# STM32H7-Board.net
KiCad netlist of a schematic drawn in Altium Designer
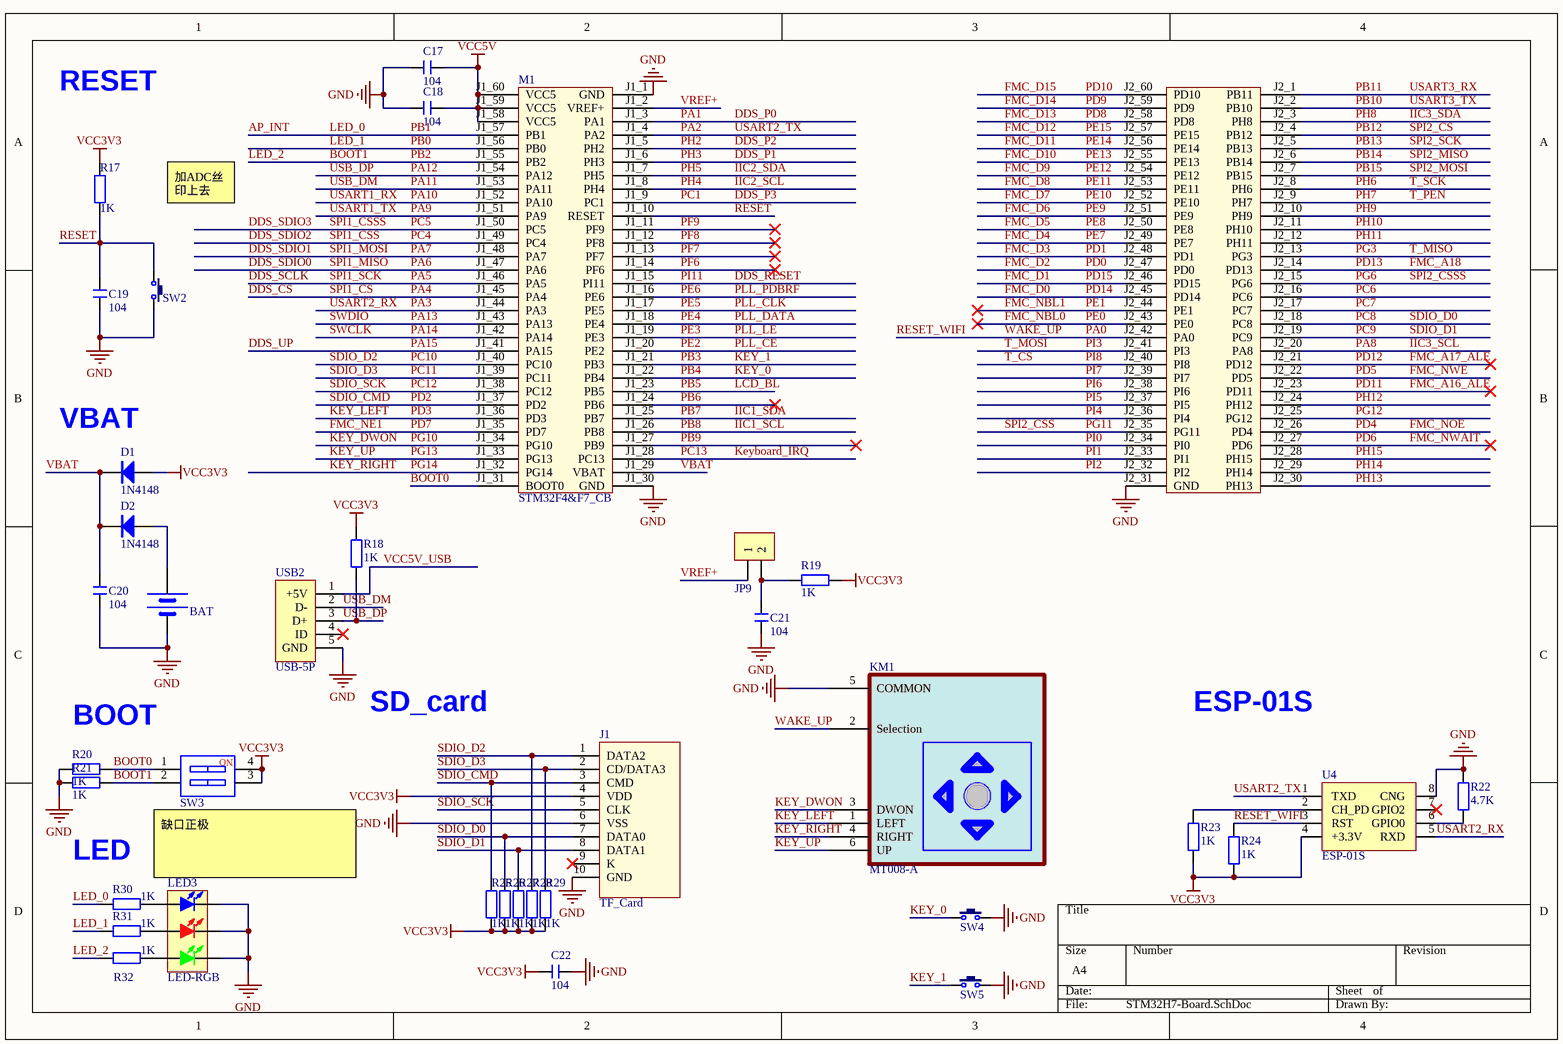
[diagram p0: STM32H7-Board.SchDoc]

(export (version "E")
  (design (tool "Eeschema 10.0.6"))
  (components
    (comp (ref "BAT") (value "BATT") (footprint "BATM") (libsource (lib "MERCURY") (part "BAT")))
    (comp (ref "C17")
      (value "104")
      (footprint "C 0603_L")
      (description "无极性贴片电容")
      (fields (field (name "版权归属") "源创客"))
      (libsource (lib "3.1   - 电阻-电容-电感") (part "C"))
    )
    (comp (ref "C18")
      (value "104")
      (footprint "C 0603_L")
      (description "无极性贴片电容")
      (fields (field (name "版权归属") "源创客"))
      (libsource (lib "3.1   - 电阻-电容-电感") (part "C"))
    )
    (comp (ref "C19")
      (value "104")
      (footprint "C 0603_L")
      (description "无极性贴片电容")
      (fields (field (name "版权归属") "源创客"))
      (libsource (lib "3.1   - 电阻-电容-电感") (part "C"))
    )
    (comp (ref "C20")
      (value "104")
      (footprint "C 0603_L")
      (description "无极性贴片电容")
      (fields (field (name "版权归属") "源创客"))
      (libsource (lib "3.1   - 电阻-电容-电感") (part "C"))
    )
    (comp (ref "C21")
      (value "104")
      (footprint "C 0603_L")
      (description "无极性贴片电容")
      (fields (field (name "版权归属") "源创客"))
      (libsource (lib "3.1   - 电阻-电容-电感") (part "C"))
    )
    (comp (ref "C22")
      (value "104")
      (footprint "C 0603_L")
      (description "无极性贴片电容")
      (fields (field (name "版权归属") "源创客"))
      (libsource (lib "电阻-电容-电感") (part "C"))
    )
    (comp (ref "D1")
      (value "1N4148")
      (footprint "SOD-323")
      (description "高速开关二极管")
      (fields (field (name "版权归属") "源创客"))
      (libsource (lib "8.1   - 二极管-整流桥") (part "1N4148"))
    )
    (comp (ref "D2")
      (value "1N4148")
      (footprint "MINI_MELF (LL34)")
      (description "高速开关二极管")
      (fields (field (name "版权归属") "源创客"))
      (libsource (lib "8.1   - 二极管-整流桥") (part "1N4148"))
    )
    (comp (ref "J1")
      (value "TF_Card")
      (footprint "Micro SD")
      (description "TF卡座")
      (fields (field (name "版权归属") "源创客"))
      (libsource (lib "4.1   - 接口类") (part "TF_Card"))
    )
    (comp (ref "JP9")
      (value "HDR-1X2")
      (footprint "HDR2.54-LI-2P")
      (description "2P接插件")
      (fields (field (name "版权归属") "源创客"))
      (libsource (lib "4.5   - 接插件-脚距2.54") (part "Header 2"))
    )
    (comp (ref "KM1")
      (value "MT008-A")
      (footprint "JOY_MT008-A")
      (libsource (lib "13.1 - 模块") (part "MT-008A"))
    )
    (comp (ref "LED3")
      (value "LED-RGB")
      (footprint "LED 5050")
      (description "三基色LED")
      (fields (field (name "版权归属") "源创客"))
      (libsource (lib "LED") (part "LED-RGB"))
    )
    (comp (ref "M1")
      (value "STM32F4&F7_CB")
      (footprint "STM32F4&F7_CB")
      (description "F429/746 Core Board")
      (libsource (lib "MERCURY") (part "STM32F4&F7_CB"))
    )
    (comp (ref "R17")
      (value "1K")
      (footprint "R 0603_L")
      (description "贴片电阻")
      (fields (field (name "版权归属") "源创客"))
      (libsource (lib "电阻-电容-电感") (part "R"))
    )
    (comp (ref "R18")
      (value "1K")
      (footprint "R 0603_L")
      (description "贴片电阻")
      (fields (field (name "版权归属") "源创客"))
      (libsource (lib "3.1   - 电阻-电容-电感") (part "R"))
    )
    (comp (ref "R19")
      (value "1K")
      (footprint "R 0603_L")
      (description "贴片电阻")
      (fields (field (name "版权归属") "源创客"))
      (libsource (lib "3.1   - 电阻-电容-电感") (part "R"))
    )
    (comp (ref "R20")
      (value "1K")
      (footprint "R 0603_L")
      (description "贴片电阻")
      (fields (field (name "版权归属") "源创客"))
      (libsource (lib "3.1   - 电阻-电容-电感") (part "R"))
    )
    (comp (ref "R21")
      (value "1K")
      (footprint "R 0603_L")
      (description "贴片电阻")
      (fields (field (name "版权归属") "源创客"))
      (libsource (lib "3.1   - 电阻-电容-电感") (part "R"))
    )
    (comp (ref "R22")
      (value "4.7K")
      (footprint "R 0603_L")
      (description "贴片电阻")
      (fields (field (name "版权归属") "源创客"))
      (libsource (lib "3.1   - 电阻-电容-电感") (part "R"))
    )
    (comp (ref "R23")
      (value "1K")
      (footprint "R 0603_L")
      (description "贴片电阻")
      (fields (field (name "版权归属") "源创客"))
      (libsource (lib "3.1   - 电阻-电容-电感") (part "R"))
    )
    (comp (ref "R24")
      (value "1K")
      (footprint "R 0603_L")
      (description "贴片电阻")
      (fields (field (name "版权归属") "源创客"))
      (libsource (lib "3.1   - 电阻-电容-电感") (part "R"))
    )
    (comp (ref "R25")
      (value "1K")
      (footprint "R 0603_L")
      (description "贴片电阻")
      (fields (field (name "版权归属") "源创客"))
      (libsource (lib "电阻-电容-电感") (part "R"))
    )
    (comp (ref "R26")
      (value "1K")
      (footprint "R 0603_L")
      (description "贴片电阻")
      (fields (field (name "版权归属") "源创客"))
      (libsource (lib "电阻-电容-电感") (part "R"))
    )
    (comp (ref "R27")
      (value "1K")
      (footprint "R 0603_L")
      (description "贴片电阻")
      (fields (field (name "版权归属") "源创客"))
      (libsource (lib "电阻-电容-电感") (part "R"))
    )
    (comp (ref "R28")
      (value "1K")
      (footprint "R 0603_L")
      (description "贴片电阻")
      (fields (field (name "版权归属") "源创客"))
      (libsource (lib "电阻-电容-电感") (part "R"))
    )
    (comp (ref "R29")
      (value "1K")
      (footprint "R 0603_L")
      (description "贴片电阻")
      (fields (field (name "版权归属") "源创客"))
      (libsource (lib "电阻-电容-电感") (part "R"))
    )
    (comp (ref "R30")
      (value "1K")
      (footprint "R 0603_L")
      (description "贴片电阻")
      (fields (field (name "版权归属") "源创客"))
      (libsource (lib "3.1   - 电阻-电容-电感") (part "R"))
    )
    (comp (ref "R31")
      (value "1K")
      (footprint "R 0603_L")
      (description "贴片电阻")
      (fields (field (name "版权归属") "源创客"))
      (libsource (lib "3.1   - 电阻-电容-电感") (part "R"))
    )
    (comp (ref "R32")
      (value "1K")
      (footprint "R 0603_L")
      (description "贴片电阻")
      (fields (field (name "版权归属") "源创客"))
      (libsource (lib "3.1   - 电阻-电容-电感") (part "R"))
    )
    (comp (ref "SW2")
      (value "3x6x5")
      (footprint "TSW SMD-3*6*2.5")
      (description "3x6轻触开关")
      (fields (field (name "版权归属") "源创客"))
      (libsource (lib "") (part "TSW 3x6_1"))
    )
    (comp (ref "SW3")
      (value "CSW-2P")
      (footprint "CSW1.27 SMD-2P")
      (description "2路编码开关")
      (fields (field (name "版权归属") "源创客"))
      (libsource (lib "5.1   - 按键-开关") (part "CSW-2P"))
    )
    (comp (ref "SW4")
      (value "3x6x5")
      (footprint "SODFL700X110-2N")
      (description "3x6轻触开关")
      (fields (field (name "版权归属") "源创客"))
      (libsource (lib "5.1   - 按键-开关") (part "TSW 3x6"))
    )
    (comp (ref "SW5")
      (value "3x6x5")
      (footprint "SODFL700X110-2N")
      (description "3x6轻触开关")
      (fields (field (name "版权归属") "源创客"))
      (libsource (lib "5.1   - 按键-开关") (part "TSW 3x6"))
    )
    (comp (ref "U4") (value "ESP-01S") (footprint "ESP-01S") (libsource (lib "13.1 - 模块") (part "ESP-01S")))
    (comp (ref "USB2")
      (value "USB-5P")
      (footprint "USB-MICRO_B")
      (description "微型USB母座")
      (fields (field (name "版权归属") "源创客"))
      (libsource (lib "4.1   - 接口类") (part "USB-5P"))
    )
  )
  (nets
    (net (code "1") (name "/AP_INT") (class "Default")
      (node (ref "M1") (pin "J1_57") (pinfunction "PB1_J1_57") (pintype "passive"))
      (node (ref "R30") (pin "2") (pinfunction "2_2") (pintype "passive"))
    )
    (net (code "2") (name "/BOOT0") (class "Default")
      (node (ref "M1") (pin "J1_31") (pinfunction "BOOT0_J1_31") (pintype "passive"))
      (node (ref "R20") (pin "2") (pinfunction "2_2") (pintype "passive"))
      (node (ref "SW3") (pin "1") (pinfunction "1_1") (pintype "passive"))
    )
    (net (code "3") (name "/BOOT1") (class "Default")
      (node (ref "M1") (pin "J1_55") (pinfunction "PB2_J1_55") (pintype "passive"))
      (node (ref "R21") (pin "2") (pinfunction "2_2") (pintype "passive"))
      (node (ref "R32") (pin "2") (pinfunction "2_2") (pintype "passive"))
      (node (ref "SW3") (pin "2") (pinfunction "2_2") (pintype "passive"))
    )
    (net (code "4") (name "/DDS_CS") (class "Default")
      (node (ref "M1") (pin "J1_45") (pinfunction "PA4_J1_45") (pintype "passive"))
    )
    (net (code "5") (name "/DDS_P0") (class "Default")
      (node (ref "M1") (pin "J1_3") (pinfunction "PA1_J1_3") (pintype "passive"))
    )
    (net (code "6") (name "/DDS_P1") (class "Default")
      (node (ref "M1") (pin "J1_6") (pinfunction "PH3_J1_6") (pintype "passive"))
    )
    (net (code "7") (name "/DDS_P2") (class "Default")
      (node (ref "M1") (pin "J1_5") (pinfunction "PH2_J1_5") (pintype "passive"))
    )
    (net (code "8") (name "/DDS_P3") (class "Default")
      (node (ref "M1") (pin "J1_9") (pinfunction "PC1_J1_9") (pintype "passive"))
    )
    (net (code "9") (name "/DDS_RESET") (class "Default")
      (node (ref "M1") (pin "J1_15") (pinfunction "PI11_J1_15") (pintype "passive"))
    )
    (net (code "10") (name "/DDS_SCLK") (class "Default")
      (node (ref "M1") (pin "J1_46") (pinfunction "PA5_J1_46") (pintype "passive"))
    )
    (net (code "11") (name "/DDS_SDIO0") (class "Default")
      (node (ref "M1") (pin "J1_47") (pinfunction "PA6_J1_47") (pintype "passive"))
    )
    (net (code "12") (name "/DDS_SDIO1") (class "Default")
      (node (ref "M1") (pin "J1_48") (pinfunction "PA7_J1_48") (pintype "passive"))
    )
    (net (code "13") (name "/DDS_SDIO2") (class "Default")
      (node (ref "M1") (pin "J1_49") (pinfunction "PC4_J1_49") (pintype "passive"))
    )
    (net (code "14") (name "/DDS_SDIO3") (class "Default")
      (node (ref "M1") (pin "J1_50") (pinfunction "PC5_J1_50") (pintype "passive"))
    )
    (net (code "15") (name "/DDS_UP") (class "Default")
      (node (ref "M1") (pin "J1_41") (pinfunction "PA15_J1_41") (pintype "passive"))
    )
    (net (code "16") (name "/FMC_A16_ALE") (class "Default")
      (node (ref "M1") (pin "J2_23") (pinfunction "PD11_J2_23") (pintype "passive+no_connect"))
    )
    (net (code "17") (name "/FMC_A17_ALE") (class "Default")
      (node (ref "M1") (pin "J2_21") (pinfunction "PD12_J2_21") (pintype "passive+no_connect"))
    )
    (net (code "18") (name "/FMC_A18") (class "Default")
      (node (ref "M1") (pin "J2_14") (pinfunction "PD13_J2_14") (pintype "passive"))
    )
    (net (code "19") (name "/FMC_D0") (class "Default")
      (node (ref "M1") (pin "J2_45") (pinfunction "PD14_J2_45") (pintype "passive"))
    )
    (net (code "20") (name "/FMC_D1") (class "Default")
      (node (ref "M1") (pin "J2_46") (pinfunction "PD15_J2_46") (pintype "passive"))
    )
    (net (code "21") (name "/FMC_D2") (class "Default")
      (node (ref "M1") (pin "J2_47") (pinfunction "PD0_J2_47") (pintype "passive"))
    )
    (net (code "22") (name "/FMC_D3") (class "Default")
      (node (ref "M1") (pin "J2_48") (pinfunction "PD1_J2_48") (pintype "passive"))
    )
    (net (code "23") (name "/FMC_D4") (class "Default")
      (node (ref "M1") (pin "J2_49") (pinfunction "PE7_J2_49") (pintype "passive"))
    )
    (net (code "24") (name "/FMC_D5") (class "Default")
      (node (ref "M1") (pin "J2_50") (pinfunction "PE8_J2_50") (pintype "passive"))
    )
    (net (code "25") (name "/FMC_D6") (class "Default")
      (node (ref "M1") (pin "J2_51") (pinfunction "PE9_J2_51") (pintype "passive"))
    )
    (net (code "26") (name "/FMC_D7") (class "Default")
      (node (ref "M1") (pin "J2_52") (pinfunction "PE10_J2_52") (pintype "passive"))
    )
    (net (code "27") (name "/FMC_D8") (class "Default")
      (node (ref "M1") (pin "J2_53") (pinfunction "PE11_J2_53") (pintype "passive"))
    )
    (net (code "28") (name "/FMC_D9") (class "Default")
      (node (ref "M1") (pin "J2_54") (pinfunction "PE12_J2_54") (pintype "passive"))
    )
    (net (code "29") (name "/FMC_D10") (class "Default")
      (node (ref "M1") (pin "J2_55") (pinfunction "PE13_J2_55") (pintype "passive"))
    )
    (net (code "30") (name "/FMC_D11") (class "Default")
      (node (ref "M1") (pin "J2_56") (pinfunction "PE14_J2_56") (pintype "passive"))
    )
    (net (code "31") (name "/FMC_D12") (class "Default")
      (node (ref "M1") (pin "J2_57") (pinfunction "PE15_J2_57") (pintype "passive"))
    )
    (net (code "32") (name "/FMC_D13") (class "Default")
      (node (ref "M1") (pin "J2_58") (pinfunction "PD8_J2_58") (pintype "passive"))
    )
    (net (code "33") (name "/FMC_D14") (class "Default")
      (node (ref "M1") (pin "J2_59") (pinfunction "PD9_J2_59") (pintype "passive"))
    )
    (net (code "34") (name "/FMC_D15") (class "Default")
      (node (ref "M1") (pin "J2_60") (pinfunction "PD10_J2_60") (pintype "passive"))
    )
    (net (code "35") (name "/FMC_NBL0") (class "Default")
      (node (ref "M1") (pin "J2_43") (pinfunction "PE0_J2_43") (pintype "passive+no_connect"))
    )
    (net (code "36") (name "/FMC_NBL1") (class "Default")
      (node (ref "M1") (pin "J2_44") (pinfunction "PE1_J2_44") (pintype "passive+no_connect"))
    )
    (net (code "37") (name "/FMC_NE1") (class "Default")
      (node (ref "M1") (pin "J1_35") (pinfunction "PD7_J1_35") (pintype "passive"))
    )
    (net (code "38") (name "/FMC_NOE") (class "Default")
      (node (ref "M1") (pin "J2_26") (pinfunction "PD4_J2_26") (pintype "passive"))
    )
    (net (code "39") (name "/FMC_NWAIT") (class "Default")
      (node (ref "M1") (pin "J2_27") (pinfunction "PD6_J2_27") (pintype "passive+no_connect"))
    )
    (net (code "40") (name "/FMC_NWE") (class "Default")
      (node (ref "M1") (pin "J2_22") (pinfunction "PD5_J2_22") (pintype "passive"))
    )
    (net (code "41") (name "/IIC1_SCL") (class "Default")
      (node (ref "M1") (pin "J1_26") (pinfunction "PB8_J1_26") (pintype "passive"))
    )
    (net (code "42") (name "/IIC1_SDA") (class "Default")
      (node (ref "M1") (pin "J1_25") (pinfunction "PB7_J1_25") (pintype "passive"))
    )
    (net (code "43") (name "/IIC2_SCL") (class "Default")
      (node (ref "M1") (pin "J1_8") (pinfunction "PH4_J1_8") (pintype "passive"))
    )
    (net (code "44") (name "/IIC2_SDA") (class "Default")
      (node (ref "M1") (pin "J1_7") (pinfunction "PH5_J1_7") (pintype "passive"))
    )
    (net (code "45") (name "/IIC3_SCL") (class "Default")
      (node (ref "M1") (pin "J2_20") (pinfunction "PA8_J2_20") (pintype "passive"))
    )
    (net (code "46") (name "/IIC3_SDA") (class "Default")
      (node (ref "M1") (pin "J2_3") (pinfunction "PH8_J2_3") (pintype "passive"))
    )
    (net (code "47") (name "/KEY_0") (class "Default")
      (node (ref "M1") (pin "J1_22") (pinfunction "PB4_J1_22") (pintype "passive"))
      (node (ref "SW4") (pin "1") (pinfunction "1_1") (pintype "passive"))
    )
    (net (code "48") (name "/KEY_1") (class "Default")
      (node (ref "M1") (pin "J1_21") (pinfunction "PB3_J1_21") (pintype "passive"))
      (node (ref "SW5") (pin "1") (pinfunction "1_1") (pintype "passive"))
    )
    (net (code "49") (name "/KEY_DWON") (class "Default")
      (node (ref "KM1") (pin "3") (pinfunction "DWON_3") (pintype "passive"))
      (node (ref "M1") (pin "J1_34") (pinfunction "PG10_J1_34") (pintype "passive"))
    )
    (net (code "50") (name "/KEY_LEFT") (class "Default")
      (node (ref "KM1") (pin "1") (pinfunction "LEFT_1") (pintype "passive"))
      (node (ref "M1") (pin "J1_36") (pinfunction "PD3_J1_36") (pintype "passive"))
    )
    (net (code "51") (name "/KEY_RIGHT") (class "Default")
      (node (ref "KM1") (pin "4") (pinfunction "RIGHT_4") (pintype "passive"))
      (node (ref "M1") (pin "J1_32") (pinfunction "PG14_J1_32") (pintype "passive"))
    )
    (net (code "52") (name "/KEY_UP") (class "Default")
      (node (ref "KM1") (pin "6") (pinfunction "UP_6") (pintype "passive"))
      (node (ref "M1") (pin "J1_33") (pinfunction "PG13_J1_33") (pintype "passive"))
    )
    (net (code "53") (name "/Keyboard_IRQ") (class "Default")
      (node (ref "M1") (pin "J1_28") (pinfunction "PC13_J1_28") (pintype "passive"))
    )
    (net (code "54") (name "/LCD_BL") (class "Default")
      (node (ref "M1") (pin "J1_23") (pinfunction "PB5_J1_23") (pintype "passive"))
    )
    (net (code "55") (name "/LED_1") (class "Default")
      (node (ref "M1") (pin "J1_56") (pinfunction "PB0_J1_56") (pintype "passive"))
      (node (ref "R31") (pin "2") (pinfunction "2_2") (pintype "passive"))
    )
    (net (code "56") (name "/PA0") (class "Default")
      (node (ref "KM1") (pin "2") (pinfunction "Selection_2") (pintype "passive"))
      (node (ref "M1") (pin "J2_42") (pinfunction "PA0_J2_42") (pintype "passive"))
      (node (ref "R24") (pin "1") (pinfunction "1_1") (pintype "passive"))
      (node (ref "U4") (pin "3") (pinfunction "RST_3") (pintype "passive"))
    )
    (net (code "57") (name "/PA2") (class "Default")
      (node (ref "M1") (pin "J1_4") (pinfunction "PA2_J1_4") (pintype "passive"))
      (node (ref "U4") (pin "1") (pinfunction "TXD_1") (pintype "passive"))
    )
    (net (code "58") (name "/PA3") (class "Default")
      (node (ref "M1") (pin "J1_44") (pinfunction "PA3_J1_44") (pintype "passive"))
      (node (ref "U4") (pin "5") (pinfunction "RXD_5") (pintype "passive"))
    )
    (net (code "59") (name "/PA9") (class "Default")
      (node (ref "M1") (pin "J1_51") (pinfunction "PA9_J1_51") (pintype "passive"))
    )
    (net (code "60") (name "/PA10") (class "Default")
      (node (ref "M1") (pin "J1_52") (pinfunction "PA10_J1_52") (pintype "passive"))
    )
    (net (code "61") (name "/PA11") (class "Default")
      (node (ref "M1") (pin "J1_53") (pinfunction "PA11_J1_53") (pintype "passive"))
      (node (ref "USB2") (pin "2") (pinfunction "D-_2") (pintype "passive"))
    )
    (net (code "62") (name "/PA12") (class "Default")
      (node (ref "M1") (pin "J1_54") (pinfunction "PA12_J1_54") (pintype "passive"))
      (node (ref "R18") (pin "2") (pinfunction "2_2") (pintype "passive"))
      (node (ref "USB2") (pin "3") (pinfunction "D+_3") (pintype "passive"))
    )
    (net (code "63") (name "/PA13") (class "Default")
      (node (ref "M1") (pin "J1_43") (pinfunction "PA13_J1_43") (pintype "passive"))
    )
    (net (code "64") (name "/PA14") (class "Default")
      (node (ref "M1") (pin "J1_42") (pinfunction "PA14_J1_42") (pintype "passive"))
    )
    (net (code "65") (name "/PB6") (class "Default")
      (node (ref "M1") (pin "J1_24") (pinfunction "PB6_J1_24") (pintype "passive+no_connect"))
    )
    (net (code "66") (name "/PB9") (class "Default")
      (node (ref "M1") (pin "J1_27") (pinfunction "PB9_J1_27") (pintype "passive+no_connect"))
    )
    (net (code "67") (name "/PB10") (class "Default")
      (node (ref "M1") (pin "J2_2") (pinfunction "PB10_J2_2") (pintype "passive"))
    )
    (net (code "68") (name "/PB11") (class "Default")
      (node (ref "M1") (pin "J2_1") (pinfunction "PB11_J2_1") (pintype "passive"))
    )
    (net (code "69") (name "/PB12") (class "Default")
      (node (ref "M1") (pin "J2_4") (pinfunction "PB12_J2_4") (pintype "passive"))
    )
    (net (code "70") (name "/PB13") (class "Default")
      (node (ref "M1") (pin "J2_5") (pinfunction "PB13_J2_5") (pintype "passive"))
    )
    (net (code "71") (name "/PB14") (class "Default")
      (node (ref "M1") (pin "J2_6") (pinfunction "PB14_J2_6") (pintype "passive"))
    )
    (net (code "72") (name "/PB15") (class "Default")
      (node (ref "M1") (pin "J2_7") (pinfunction "PB15_J2_7") (pintype "passive"))
    )
    (net (code "73") (name "/PC6") (class "Default")
      (node (ref "M1") (pin "J2_16") (pinfunction "PC6_J2_16") (pintype "passive"))
    )
    (net (code "74") (name "/PC7") (class "Default")
      (node (ref "M1") (pin "J2_17") (pinfunction "PC7_J2_17") (pintype "passive"))
    )
    (net (code "75") (name "/PC8") (class "Default")
      (node (ref "J1") (pin "7") (pinfunction "DATA0_7") (pintype "passive"))
      (node (ref "M1") (pin "J2_18") (pinfunction "PC8_J2_18") (pintype "passive"))
      (node (ref "R26") (pin "2") (pinfunction "2_2") (pintype "passive"))
    )
    (net (code "76") (name "/PC9") (class "Default")
      (node (ref "J1") (pin "8") (pinfunction "DATA1_8") (pintype "passive"))
      (node (ref "M1") (pin "J2_19") (pinfunction "PC9_J2_19") (pintype "passive"))
      (node (ref "R27") (pin "2") (pinfunction "2_2") (pintype "passive"))
    )
    (net (code "77") (name "/PC10") (class "Default")
      (node (ref "J1") (pin "1") (pinfunction "DATA2_1") (pintype "passive"))
      (node (ref "M1") (pin "J1_40") (pinfunction "PC10_J1_40") (pintype "passive"))
      (node (ref "R28") (pin "2") (pinfunction "2_2") (pintype "passive"))
    )
    (net (code "78") (name "/PC11") (class "Default")
      (node (ref "J1") (pin "2") (pinfunction "CD/DATA3_2") (pintype "passive"))
      (node (ref "M1") (pin "J1_39") (pinfunction "PC11_J1_39") (pintype "passive"))
      (node (ref "R29") (pin "2") (pinfunction "2_2") (pintype "passive"))
    )
    (net (code "79") (name "/PC12") (class "Default")
      (node (ref "J1") (pin "5") (pinfunction "CLK_5") (pintype "passive"))
      (node (ref "M1") (pin "J1_38") (pinfunction "PC12_J1_38") (pintype "passive"))
    )
    (net (code "80") (name "/PD2") (class "Default")
      (node (ref "J1") (pin "3") (pinfunction "CMD_3") (pintype "passive"))
      (node (ref "M1") (pin "J1_37") (pinfunction "PD2_J1_37") (pintype "passive"))
      (node (ref "R25") (pin "2") (pinfunction "2_2") (pintype "passive"))
    )
    (net (code "81") (name "/PE2") (class "Default")
      (node (ref "M1") (pin "J1_20") (pinfunction "PE2_J1_20") (pintype "passive"))
    )
    (net (code "82") (name "/PE3") (class "Default")
      (node (ref "M1") (pin "J1_19") (pinfunction "PE3_J1_19") (pintype "passive"))
    )
    (net (code "83") (name "/PE4") (class "Default")
      (node (ref "M1") (pin "J1_18") (pinfunction "PE4_J1_18") (pintype "passive"))
    )
    (net (code "84") (name "/PE5") (class "Default")
      (node (ref "M1") (pin "J1_17") (pinfunction "PE5_J1_17") (pintype "passive"))
    )
    (net (code "85") (name "/PE6") (class "Default")
      (node (ref "M1") (pin "J1_16") (pinfunction "PE6_J1_16") (pintype "passive"))
    )
    (net (code "86") (name "/PF6") (class "Default")
      (node (ref "M1") (pin "J1_14") (pinfunction "PF6_J1_14") (pintype "passive+no_connect"))
    )
    (net (code "87") (name "/PF7") (class "Default")
      (node (ref "M1") (pin "J1_13") (pinfunction "PF7_J1_13") (pintype "passive+no_connect"))
    )
    (net (code "88") (name "/PF8") (class "Default")
      (node (ref "M1") (pin "J1_12") (pinfunction "PF8_J1_12") (pintype "passive+no_connect"))
    )
    (net (code "89") (name "/PF9") (class "Default")
      (node (ref "M1") (pin "J1_11") (pinfunction "PF9_J1_11") (pintype "passive+no_connect"))
    )
    (net (code "90") (name "/PG3") (class "Default")
      (node (ref "M1") (pin "J2_13") (pinfunction "PG3_J2_13") (pintype "passive"))
    )
    (net (code "91") (name "/PG6") (class "Default")
      (node (ref "M1") (pin "J2_15") (pinfunction "PG6_J2_15") (pintype "passive"))
    )
    (net (code "92") (name "/PG11") (class "Default")
      (node (ref "M1") (pin "J2_35") (pinfunction "PG11_J2_35") (pintype "passive"))
    )
    (net (code "93") (name "/PG12") (class "Default")
      (node (ref "M1") (pin "J2_25") (pinfunction "PG12_J2_25") (pintype "passive"))
    )
    (net (code "94") (name "/PH6") (class "Default")
      (node (ref "M1") (pin "J2_8") (pinfunction "PH6_J2_8") (pintype "passive"))
    )
    (net (code "95") (name "/PH7") (class "Default")
      (node (ref "M1") (pin "J2_9") (pinfunction "PH7_J2_9") (pintype "passive"))
    )
    (net (code "96") (name "/PH9") (class "Default")
      (node (ref "M1") (pin "J2_10") (pinfunction "PH9_J2_10") (pintype "passive"))
    )
    (net (code "97") (name "/PH10") (class "Default")
      (node (ref "M1") (pin "J2_11") (pinfunction "PH10_J2_11") (pintype "passive"))
    )
    (net (code "98") (name "/PH11") (class "Default")
      (node (ref "M1") (pin "J2_12") (pinfunction "PH11_J2_12") (pintype "passive"))
    )
    (net (code "99") (name "/PH12") (class "Default")
      (node (ref "M1") (pin "J2_24") (pinfunction "PH12_J2_24") (pintype "passive"))
    )
    (net (code "100") (name "/PH13") (class "Default")
      (node (ref "M1") (pin "J2_30") (pinfunction "PH13_J2_30") (pintype "passive"))
    )
    (net (code "101") (name "/PH14") (class "Default")
      (node (ref "M1") (pin "J2_29") (pinfunction "PH14_J2_29") (pintype "passive"))
    )
    (net (code "102") (name "/PH15") (class "Default")
      (node (ref "M1") (pin "J2_28") (pinfunction "PH15_J2_28") (pintype "passive"))
    )
    (net (code "103") (name "/PI0") (class "Default")
      (node (ref "M1") (pin "J2_34") (pinfunction "PI0_J2_34") (pintype "passive"))
    )
    (net (code "104") (name "/PI1") (class "Default")
      (node (ref "M1") (pin "J2_33") (pinfunction "PI1_J2_33") (pintype "passive"))
    )
    (net (code "105") (name "/PI2") (class "Default")
      (node (ref "M1") (pin "J2_32") (pinfunction "PI2_J2_32") (pintype "passive"))
    )
    (net (code "106") (name "/PI3") (class "Default")
      (node (ref "M1") (pin "J2_41") (pinfunction "PI3_J2_41") (pintype "passive"))
    )
    (net (code "107") (name "/PI4") (class "Default")
      (node (ref "M1") (pin "J2_36") (pinfunction "PI4_J2_36") (pintype "passive"))
    )
    (net (code "108") (name "/PI5") (class "Default")
      (node (ref "M1") (pin "J2_37") (pinfunction "PI5_J2_37") (pintype "passive"))
    )
    (net (code "109") (name "/PI6") (class "Default")
      (node (ref "M1") (pin "J2_38") (pinfunction "PI6_J2_38") (pintype "passive"))
    )
    (net (code "110") (name "/PI7") (class "Default")
      (node (ref "M1") (pin "J2_39") (pinfunction "PI7_J2_39") (pintype "passive"))
    )
    (net (code "111") (name "/PI8") (class "Default")
      (node (ref "M1") (pin "J2_40") (pinfunction "PI8_J2_40") (pintype "passive"))
    )
    (net (code "112") (name "/RESET") (class "Default")
      (node (ref "C19") (pin "2") (pinfunction "2_2") (pintype "passive"))
      (node (ref "M1") (pin "J1_10") (pinfunction "RESET_J1_10") (pintype "passive"))
      (node (ref "R17") (pin "1") (pinfunction "1_1") (pintype "passive"))
      (node (ref "SW2") (pin "1") (pinfunction "1_1") (pintype "passive"))
    )
    (net (code "113") (name "/VBAT") (class "Default")
      (node (ref "C20") (pin "2") (pinfunction "2_2") (pintype "passive"))
      (node (ref "D1") (pin "2") (pinfunction "K_2") (pintype "passive"))
      (node (ref "D2") (pin "2") (pinfunction "K_2") (pintype "passive"))
      (node (ref "M1") (pin "J1_29") (pinfunction "VBAT_J1_29") (pintype "passive"))
    )
    (net (code "114") (name "/VCC5V_USB") (class "Default")
      (node (ref "USB2") (pin "1") (pinfunction "+5V_1") (pintype "passive"))
    )
    (net (code "115") (name "/VREF+") (class "Default")
      (node (ref "JP9") (pin "1") (pinfunction "1_1") (pintype "passive"))
      (node (ref "M1") (pin "J1_2") (pinfunction "VREF+_J1_2") (pintype "passive"))
    )
    (net (code "116") (name "GND") (class "Default")
      (node (ref "BAT") (pin "2") (pinfunction "GND_2") (pintype "passive"))
      (node (ref "C17") (pin "1") (pinfunction "1_1") (pintype "passive"))
      (node (ref "C18") (pin "1") (pinfunction "1_1") (pintype "passive"))
      (node (ref "C19") (pin "1") (pinfunction "1_1") (pintype "passive"))
      (node (ref "C20") (pin "1") (pinfunction "1_1") (pintype "passive"))
      (node (ref "C21") (pin "1") (pinfunction "1_1") (pintype "passive"))
      (node (ref "C22") (pin "2") (pinfunction "2_2") (pintype "passive"))
      (node (ref "J1") (pin "10") (pinfunction "GND_10") (pintype "passive"))
      (node (ref "J1") (pin "6") (pinfunction "VSS_6") (pintype "passive"))
      (node (ref "KM1") (pin "5") (pinfunction "COMMON_5") (pintype "passive"))
      (node (ref "LED3") (pin "2") (pinfunction "BULE_K_2") (pintype "passive"))
      (node (ref "LED3") (pin "4") (pinfunction "RED_K_4") (pintype "passive"))
      (node (ref "LED3") (pin "6") (pinfunction "GREEN_K_6") (pintype "passive"))
      (node (ref "M1") (pin "J1_1") (pinfunction "GND_J1_1") (pintype "passive"))
      (node (ref "M1") (pin "J1_30") (pinfunction "GND_J1_30") (pintype "passive"))
      (node (ref "M1") (pin "J2_31") (pinfunction "GND_J2_31") (pintype "passive"))
      (node (ref "R20") (pin "1") (pinfunction "1_1") (pintype "passive"))
      (node (ref "R21") (pin "1") (pinfunction "1_1") (pintype "passive"))
      (node (ref "R22") (pin "2") (pinfunction "2_2") (pintype "passive"))
      (node (ref "SW2") (pin "2") (pinfunction "2_2") (pintype "passive"))
      (node (ref "SW4") (pin "2") (pinfunction "2_2") (pintype "passive"))
      (node (ref "SW5") (pin "2") (pinfunction "2_2") (pintype "passive"))
      (node (ref "U4") (pin "8") (pinfunction "CNG_8") (pintype "passive"))
      (node (ref "USB2") (pin "5") (pinfunction "GND_5") (pintype "passive"))
    )
    (net (code "117") (name "Net-(BAT-VCC)") (class "Default")
      (node (ref "BAT") (pin "1") (pinfunction "VCC_1") (pintype "passive"))
      (node (ref "D2") (pin "1") (pinfunction "A_1") (pintype "passive"))
    )
    (net (code "118") (name "Net-(C21-Pad2)") (class "Default")
      (node (ref "C21") (pin "2") (pinfunction "2_2") (pintype "passive"))
      (node (ref "JP9") (pin "2") (pinfunction "2_2") (pintype "passive"))
      (node (ref "R19") (pin "1") (pinfunction "1_1") (pintype "passive"))
    )
    (net (code "119") (name "Net-(LED3-BULE_A)") (class "Default")
      (node (ref "LED3") (pin "1") (pinfunction "BULE_A_1") (pintype "passive"))
      (node (ref "R30") (pin "1") (pinfunction "1_1") (pintype "passive"))
    )
    (net (code "120") (name "Net-(LED3-GREEN_A)") (class "Default")
      (node (ref "LED3") (pin "5") (pinfunction "GREEN_A_5") (pintype "passive"))
      (node (ref "R32") (pin "1") (pinfunction "1_1") (pintype "passive"))
    )
    (net (code "121") (name "Net-(LED3-RED_A)") (class "Default")
      (node (ref "LED3") (pin "3") (pinfunction "RED_A_3") (pintype "passive"))
      (node (ref "R31") (pin "1") (pinfunction "1_1") (pintype "passive"))
    )
    (net (code "122") (name "Net-(U4-CH_PD)") (class "Default")
      (node (ref "R23") (pin "1") (pinfunction "1_1") (pintype "passive"))
      (node (ref "U4") (pin "2") (pinfunction "CH_PD_2") (pintype "passive"))
    )
    (net (code "123") (name "Net-(U4-GPIO0)") (class "Default")
      (node (ref "R22") (pin "1") (pinfunction "1_1") (pintype "passive"))
      (node (ref "U4") (pin "6") (pinfunction "GPIO0_6") (pintype "passive"))
    )
    (net (code "124") (name "VCC3V3") (class "Default")
      (node (ref "C22") (pin "1") (pinfunction "1_1") (pintype "passive"))
      (node (ref "D1") (pin "1") (pinfunction "A_1") (pintype "passive"))
      (node (ref "J1") (pin "4") (pinfunction "VDD_4") (pintype "passive"))
      (node (ref "R17") (pin "2") (pinfunction "2_2") (pintype "passive"))
      (node (ref "R18") (pin "1") (pinfunction "1_1") (pintype "passive"))
      (node (ref "R19") (pin "2") (pinfunction "2_2") (pintype "passive"))
      (node (ref "R23") (pin "2") (pinfunction "2_2") (pintype "passive"))
      (node (ref "R24") (pin "2") (pinfunction "2_2") (pintype "passive"))
      (node (ref "R25") (pin "1") (pinfunction "1_1") (pintype "passive"))
      (node (ref "R26") (pin "1") (pinfunction "1_1") (pintype "passive"))
      (node (ref "R27") (pin "1") (pinfunction "1_1") (pintype "passive"))
      (node (ref "R28") (pin "1") (pinfunction "1_1") (pintype "passive"))
      (node (ref "R29") (pin "1") (pinfunction "1_1") (pintype "passive"))
      (node (ref "SW3") (pin "3") (pinfunction "3_3") (pintype "passive"))
      (node (ref "SW3") (pin "4") (pinfunction "4_4") (pintype "passive"))
      (node (ref "U4") (pin "4") (pinfunction "+3.3V_4") (pintype "passive"))
    )
    (net (code "125") (name "VCC5V") (class "Default")
      (node (ref "C17") (pin "2") (pinfunction "2_2") (pintype "passive"))
      (node (ref "C18") (pin "2") (pinfunction "2_2") (pintype "passive"))
      (node (ref "M1") (pin "J1_58") (pinfunction "VCC5_J1_58") (pintype "passive"))
      (node (ref "M1") (pin "J1_59") (pinfunction "VCC5_J1_59") (pintype "passive"))
      (node (ref "M1") (pin "J1_60") (pinfunction "VCC5_J1_60") (pintype "passive"))
    )
    (net (code "126") (name "unconnected-(J1-K-Pad9)") (class "Default")
      (node (ref "J1") (pin "9") (pinfunction "K_9") (pintype "passive+no_connect"))
    )
    (net (code "127") (name "unconnected-(U4-GPIO2-Pad7)") (class "Default")
      (node (ref "U4") (pin "7") (pinfunction "GPIO2_7") (pintype "passive+no_connect"))
    )
    (net (code "128") (name "unconnected-(USB2-ID-Pad4)") (class "Default")
      (node (ref "USB2") (pin "4") (pinfunction "ID_4") (pintype "passive+no_connect"))
    )
  )
)
